# zumy_carrier_board.net
KiCad netlist of a schematic drawn in EAGLE
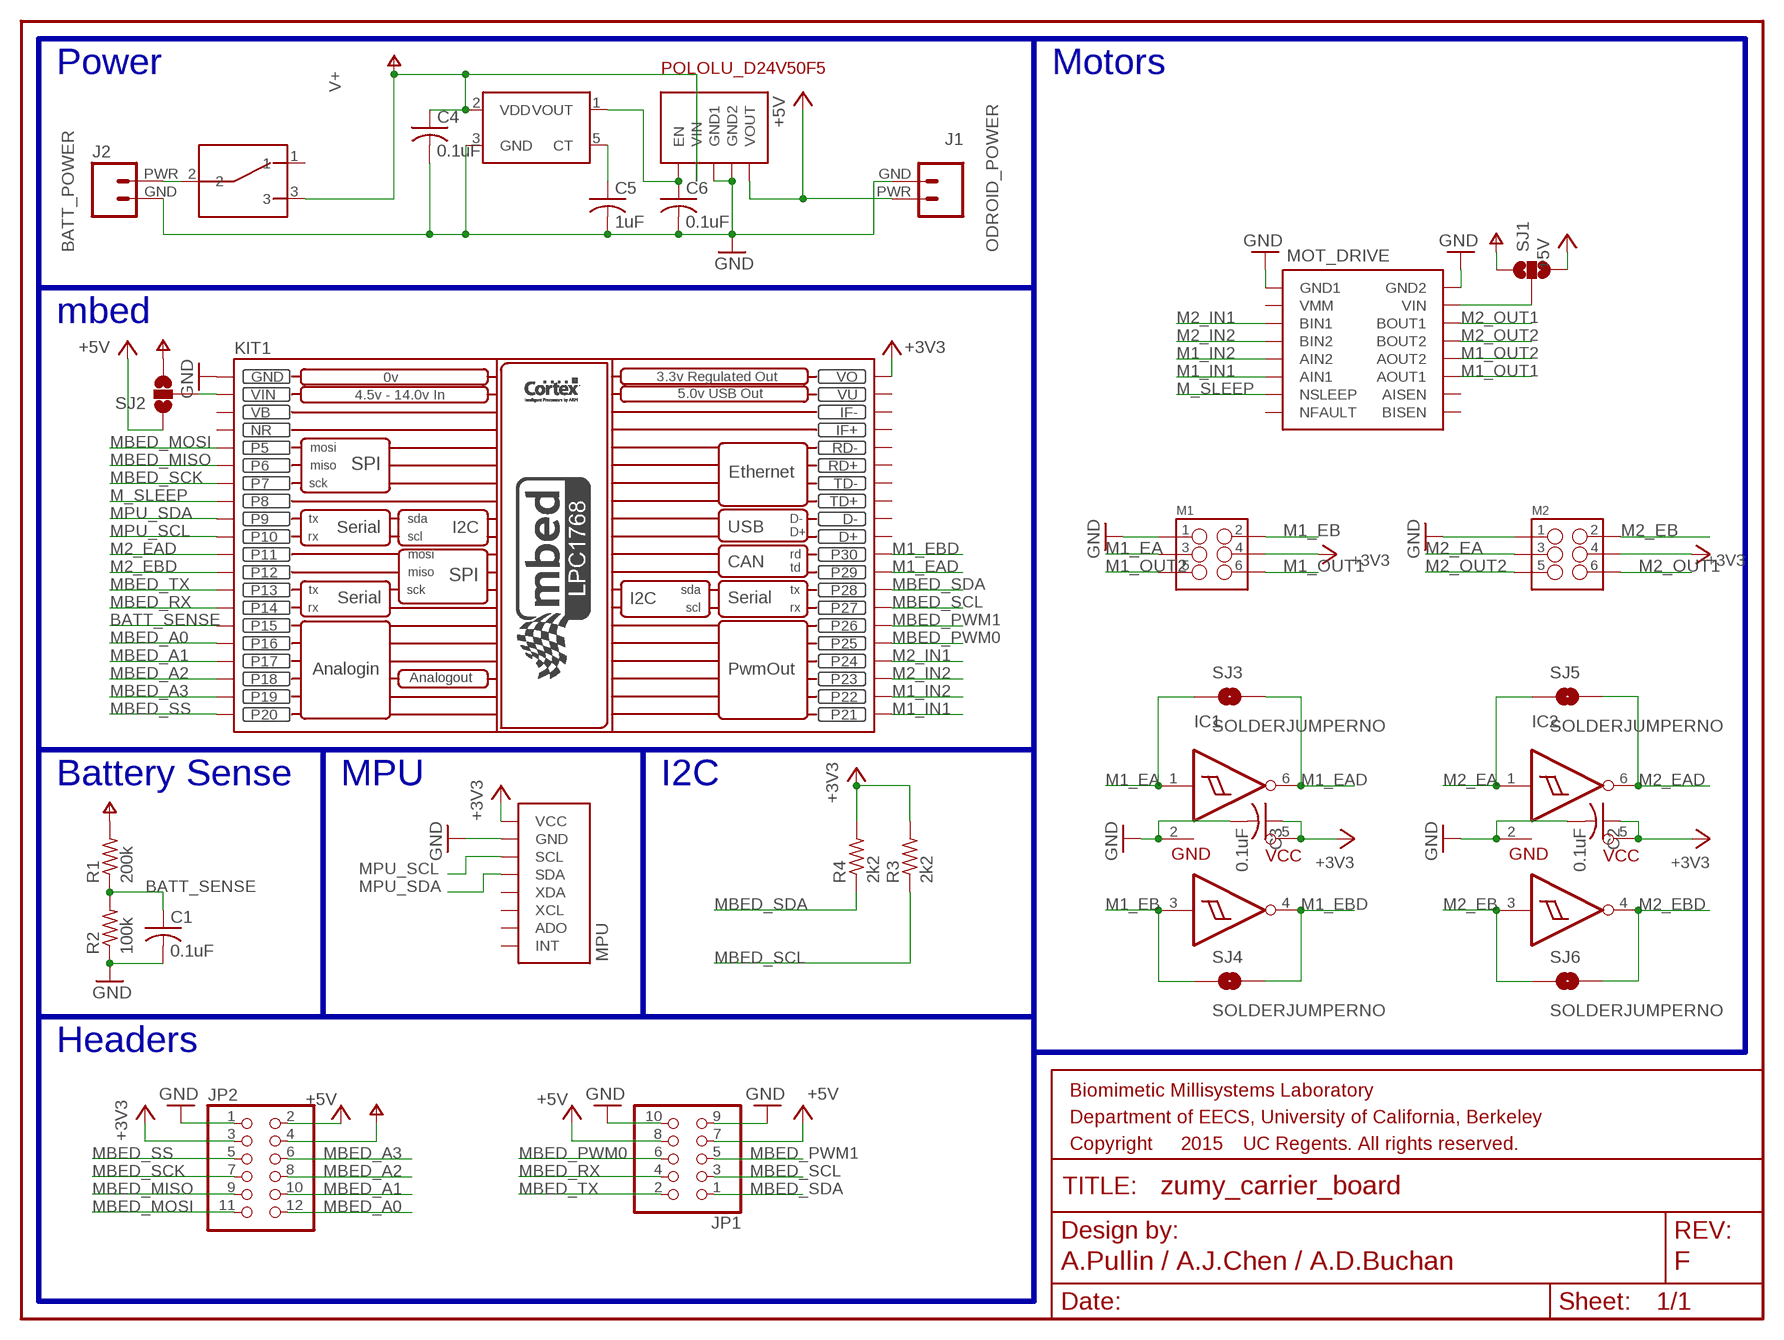
[diagram p0: schematic, sheet 1]

(export (version "E")
  (design (tool "Eeschema 10.0.6"))
  (components
    (comp (ref "C1")
      (value "0.1uF")
      (footprint "eagle-import:C1206")
      (libsource (lib "eagle-import") (part "C-USC1206"))
    )
    (comp (ref "C2")
      (value "0.1uF")
      (footprint "eagle-import:C1206")
      (libsource (lib "eagle-import") (part "C-USC1206"))
    )
    (comp (ref "C3")
      (value "0.1uF")
      (footprint "eagle-import:C1206")
      (libsource (lib "eagle-import") (part "C-USC1206"))
    )
    (comp (ref "C4")
      (value "0.1uF")
      (footprint "eagle-import:C1206")
      (libsource (lib "eagle-import") (part "C-USC1206"))
    )
    (comp (ref "C5")
      (value "1uF")
      (footprint "eagle-import:C1206")
      (libsource (lib "eagle-import") (part "C-USC1206"))
    )
    (comp (ref "C6")
      (value "0.1uF")
      (footprint "eagle-import:C1206")
      (libsource (lib "eagle-import") (part "C-USC1206"))
    )
    (comp (ref "IC1")
      (value "SN74AUP2G17")
      (footprint "eagle-import:SC-70-6")
      (libsource (lib "eagle-import") (part "SN74AUP2G17"))
    )
    (comp (ref "IC2")
      (value "SN74AUP2G17")
      (footprint "eagle-import:SC-70-6")
      (libsource (lib "eagle-import") (part "SN74AUP2G17"))
    )
    (comp (ref "J1")
      (value "ODROID_POWER")
      (footprint "eagle-import:ODOIRD_PWR")
      (libsource (lib "eagle-import") (part "ODROID_POWER"))
    )
    (comp (ref "J2")
      (value "BATT_POWER")
      (footprint "eagle-import:BATT_POWER")
      (libsource (lib "eagle-import") (part "BATT_POWER"))
    )
    (comp (ref "JP1")
      (value "PINHD-2X5")
      (footprint "eagle-import:2X05")
      (libsource (lib "eagle-import") (part "PINHD-2X5"))
    )
    (comp (ref "JP2")
      (value "PINHD-2X6")
      (footprint "eagle-import:2X06")
      (libsource (lib "eagle-import") (part "PINHD-2X6"))
    )
    (comp (ref "KIT1")
      (value "MBED_NXP_LPC1768")
      (footprint "eagle-import:MBED-KIT")
      (libsource (lib "eagle-import") (part "MBED_NXP_LPC1768"))
    )
    (comp (ref "M1")
      (value "M03X2SHROUD")
      (footprint "eagle-import:2X3-SHROUDED")
      (libsource (lib "eagle-import") (part "M03X2SHROUD"))
    )
    (comp (ref "M2")
      (value "M03X2SHROUD")
      (footprint "eagle-import:2X3-SHROUDED")
      (libsource (lib "eagle-import") (part "M03X2SHROUD"))
    )
    (comp (ref "MOT_DRIVE")
      (value "POLOLU_DRV8833_MODULE")
      (footprint "eagle-import:POLOLU_DRV8833_MODULE")
      (libsource (lib "eagle-import") (part "POLOLU_DRV8833_MODULE"))
    )
    (comp (ref "MPU")
      (value "ITG/MPU_MODULE")
      (footprint "eagle-import:ITG_MPU_MODULE")
      (libsource (lib "eagle-import") (part "ITG/MPU_MODULE"))
    )
    (comp (ref "R1")
      (value "200k")
      (footprint "eagle-import:R1206")
      (libsource (lib "eagle-import") (part "R-US_R1206"))
    )
    (comp (ref "R2")
      (value "100k")
      (footprint "eagle-import:R1206")
      (libsource (lib "eagle-import") (part "R-US_R1206"))
    )
    (comp (ref "R3")
      (value "2k2")
      (footprint "eagle-import:R1206")
      (libsource (lib "eagle-import") (part "R-US_R1206"))
    )
    (comp (ref "R4")
      (value "2k2")
      (footprint "eagle-import:R1206")
      (libsource (lib "eagle-import") (part "R-US_R1206"))
    )
    (comp (ref "SJ1")
      (value "SOLDERJUMPER_2WAYT")
      (footprint "eagle-import:SJ_2")
      (libsource (lib "eagle-import") (part "SOLDERJUMPER_2WAYT"))
    )
    (comp (ref "SJ2")
      (value "SOLDERJUMPER_2WAYT")
      (footprint "eagle-import:SJ_2")
      (libsource (lib "eagle-import") (part "SOLDERJUMPER_2WAYT"))
    )
    (comp (ref "SJ3")
      (value "SOLDERJUMPERNO")
      (footprint "eagle-import:SJ_2S-NO")
      (libsource (lib "eagle-import") (part "SOLDERJUMPERNO"))
    )
    (comp (ref "SJ4")
      (value "SOLDERJUMPERNO")
      (footprint "eagle-import:SJ_2S-NO")
      (libsource (lib "eagle-import") (part "SOLDERJUMPERNO"))
    )
    (comp (ref "SJ5")
      (value "SOLDERJUMPERNO")
      (footprint "eagle-import:SJ_2S-NO")
      (libsource (lib "eagle-import") (part "SOLDERJUMPERNO"))
    )
    (comp (ref "SJ6")
      (value "SOLDERJUMPERNO")
      (footprint "eagle-import:SJ_2S-NO")
      (libsource (lib "eagle-import") (part "SOLDERJUMPERNO"))
    )
    (comp (ref "SW1")
      (value "500SSP1S1M6QEA")
      (footprint "eagle-import:500SSP1S1M6QEA_SWITCH")
      (libsource (lib "eagle-import") (part "500SSP1S1M6QEA"))
    )
    (comp (ref "U$2")
      (value "BD5260G")
      (footprint "eagle-import:SOT23-5")
      (libsource (lib "eagle-import") (part "BD5260G"))
    )
    (comp (ref "U$5")
      (value "POLOLU_D24V50F5")
      (footprint "eagle-import:POLOLU_D24V50F5")
      (libsource (lib "eagle-import") (part "POLOLU_D24V50F5"))
    )
  )
  (nets
    (net (code "1") (name "+3V3") (class "Default")
      (node (ref "C2") (pin "1") (pinfunction "1_1") (pintype "passive"))
      (node (ref "C3") (pin "1") (pinfunction "1_1") (pintype "passive"))
      (node (ref "IC1") (pin "5") (pinfunction "VCC_5") (pintype "output"))
      (node (ref "IC2") (pin "5") (pinfunction "VCC_5") (pintype "output"))
      (node (ref "JP2") (pin "3") (pinfunction "3_3") (pintype "passive"))
      (node (ref "KIT1") (pin "VOUT") (pinfunction "VO_VOUT") (pintype "power_in"))
      (node (ref "M1") (pin "4") (pinfunction "4_4") (pintype "bidirectional"))
      (node (ref "M2") (pin "4") (pinfunction "4_4") (pintype "bidirectional"))
      (node (ref "MPU") (pin "VCC") (pinfunction "VCC_VCC") (pintype "bidirectional"))
      (node (ref "R3") (pin "2") (pinfunction "2_2") (pintype "passive"))
      (node (ref "R4") (pin "2") (pinfunction "2_2") (pintype "passive"))
    )
    (net (code "2") (name "+5V") (class "Default")
      (node (ref "J1") (pin "PWR") (pinfunction "PWR_PWR") (pintype "passive"))
      (node (ref "JP1") (pin "7") (pinfunction "7_7") (pintype "passive"))
      (node (ref "JP1") (pin "8") (pinfunction "8_8") (pintype "passive"))
      (node (ref "JP2") (pin "2") (pinfunction "2_2") (pintype "passive"))
      (node (ref "SJ1") (pin "3") (pinfunction "3_3") (pintype "passive"))
      (node (ref "SJ2") (pin "1") (pinfunction "1_1") (pintype "passive"))
      (node (ref "U$5") (pin "VOUT") (pinfunction "VOUT_VOUT") (pintype "bidirectional"))
    )
    (net (code "3") (name "/BATT_SENSE") (class "Default")
      (node (ref "C1") (pin "1") (pinfunction "1_1") (pintype "passive"))
      (node (ref "KIT1") (pin "P$15") (pinfunction "P15_P$15") (pintype "bidirectional"))
      (node (ref "R1") (pin "1") (pinfunction "1_1") (pintype "passive"))
      (node (ref "R2") (pin "2") (pinfunction "2_2") (pintype "passive"))
    )
    (net (code "4") (name "/M1_EA") (class "Default")
      (node (ref "IC1") (pin "1") (pinfunction "1A_1") (pintype "input"))
      (node (ref "M1") (pin "3") (pinfunction "3_3") (pintype "bidirectional"))
      (node (ref "SJ3") (pin "1") (pinfunction "1_1") (pintype "passive"))
    )
    (net (code "5") (name "/M1_EAD") (class "Default")
      (node (ref "IC1") (pin "6") (pinfunction "1Y_6") (pintype "output"))
      (node (ref "KIT1") (pin "P$29") (pinfunction "P29_P$29") (pintype "bidirectional"))
      (node (ref "SJ3") (pin "2") (pinfunction "2_2") (pintype "passive"))
    )
    (net (code "6") (name "/M1_EB") (class "Default")
      (node (ref "IC1") (pin "3") (pinfunction "2A_3") (pintype "input"))
      (node (ref "M1") (pin "2") (pinfunction "2_2") (pintype "bidirectional"))
      (node (ref "SJ4") (pin "1") (pinfunction "1_1") (pintype "passive"))
    )
    (net (code "7") (name "/M1_EBD") (class "Default")
      (node (ref "IC1") (pin "4") (pinfunction "2Y_4") (pintype "output"))
      (node (ref "KIT1") (pin "P$30") (pinfunction "P30_P$30") (pintype "bidirectional"))
      (node (ref "SJ4") (pin "2") (pinfunction "2_2") (pintype "passive"))
    )
    (net (code "8") (name "/M1_IN1") (class "Default")
      (node (ref "KIT1") (pin "P$21") (pinfunction "P21_P$21") (pintype "bidirectional"))
      (node (ref "MOT_DRIVE") (pin "AIN1") (pinfunction "AIN1_AIN1") (pintype "bidirectional"))
    )
    (net (code "9") (name "/M1_IN2") (class "Default")
      (node (ref "KIT1") (pin "P$22") (pinfunction "P22_P$22") (pintype "bidirectional"))
      (node (ref "MOT_DRIVE") (pin "AIN2") (pinfunction "AIN2_AIN2") (pintype "bidirectional"))
    )
    (net (code "10") (name "/M1_OUT1") (class "Default")
      (node (ref "M1") (pin "6") (pinfunction "6_6") (pintype "bidirectional"))
      (node (ref "MOT_DRIVE") (pin "AOUT1") (pinfunction "AOUT1_AOUT1") (pintype "bidirectional"))
    )
    (net (code "11") (name "/M1_OUT2") (class "Default")
      (node (ref "M1") (pin "5") (pinfunction "5_5") (pintype "bidirectional"))
      (node (ref "MOT_DRIVE") (pin "AOUT2") (pinfunction "AOUT2_AOUT2") (pintype "bidirectional"))
    )
    (net (code "12") (name "/M2_EA") (class "Default")
      (node (ref "IC2") (pin "1") (pinfunction "1A_1") (pintype "input"))
      (node (ref "M2") (pin "3") (pinfunction "3_3") (pintype "bidirectional"))
      (node (ref "SJ5") (pin "1") (pinfunction "1_1") (pintype "passive"))
    )
    (net (code "13") (name "/M2_EAD") (class "Default")
      (node (ref "IC2") (pin "6") (pinfunction "1Y_6") (pintype "output"))
      (node (ref "KIT1") (pin "P$11") (pinfunction "P11_P$11") (pintype "bidirectional"))
      (node (ref "SJ5") (pin "2") (pinfunction "2_2") (pintype "passive"))
    )
    (net (code "14") (name "/M2_EB") (class "Default")
      (node (ref "IC2") (pin "3") (pinfunction "2A_3") (pintype "input"))
      (node (ref "M2") (pin "2") (pinfunction "2_2") (pintype "bidirectional"))
      (node (ref "SJ6") (pin "1") (pinfunction "1_1") (pintype "passive"))
    )
    (net (code "15") (name "/M2_EBD") (class "Default")
      (node (ref "IC2") (pin "4") (pinfunction "2Y_4") (pintype "output"))
      (node (ref "KIT1") (pin "P$12") (pinfunction "P12_P$12") (pintype "bidirectional"))
      (node (ref "SJ6") (pin "2") (pinfunction "2_2") (pintype "passive"))
    )
    (net (code "16") (name "/M2_IN1") (class "Default")
      (node (ref "KIT1") (pin "P$24") (pinfunction "P24_P$24") (pintype "bidirectional"))
      (node (ref "MOT_DRIVE") (pin "BIN1") (pinfunction "BIN1_BIN1") (pintype "bidirectional"))
    )
    (net (code "17") (name "/M2_IN2") (class "Default")
      (node (ref "KIT1") (pin "P$23") (pinfunction "P23_P$23") (pintype "bidirectional"))
      (node (ref "MOT_DRIVE") (pin "BIN2") (pinfunction "BIN2_BIN2") (pintype "bidirectional"))
    )
    (net (code "18") (name "/M2_OUT1") (class "Default")
      (node (ref "M2") (pin "6") (pinfunction "6_6") (pintype "bidirectional"))
      (node (ref "MOT_DRIVE") (pin "BOUT1") (pinfunction "BOUT1_BOUT1") (pintype "bidirectional"))
    )
    (net (code "19") (name "/M2_OUT2") (class "Default")
      (node (ref "M2") (pin "5") (pinfunction "5_5") (pintype "bidirectional"))
      (node (ref "MOT_DRIVE") (pin "BOUT2") (pinfunction "BOUT2_BOUT2") (pintype "bidirectional"))
    )
    (net (code "20") (name "/MBED_A0") (class "Default")
      (node (ref "JP2") (pin "12") (pinfunction "12_12") (pintype "passive"))
      (node (ref "KIT1") (pin "P$16") (pinfunction "P16_P$16") (pintype "bidirectional"))
    )
    (net (code "21") (name "/MBED_A1") (class "Default")
      (node (ref "JP2") (pin "10") (pinfunction "10_10") (pintype "passive"))
      (node (ref "KIT1") (pin "P$17") (pinfunction "P17_P$17") (pintype "bidirectional"))
    )
    (net (code "22") (name "/MBED_A2") (class "Default")
      (node (ref "JP2") (pin "8") (pinfunction "8_8") (pintype "passive"))
      (node (ref "KIT1") (pin "P$18") (pinfunction "P18_P$18") (pintype "bidirectional"))
    )
    (net (code "23") (name "/MBED_A3") (class "Default")
      (node (ref "JP2") (pin "6") (pinfunction "6_6") (pintype "passive"))
      (node (ref "KIT1") (pin "P$19") (pinfunction "P19_P$19") (pintype "bidirectional"))
    )
    (net (code "24") (name "/MBED_MISO") (class "Default")
      (node (ref "JP2") (pin "9") (pinfunction "9_9") (pintype "passive"))
      (node (ref "KIT1") (pin "P$6") (pinfunction "P6_P$6") (pintype "bidirectional"))
    )
    (net (code "25") (name "/MBED_MOSI") (class "Default")
      (node (ref "JP2") (pin "11") (pinfunction "11_11") (pintype "passive"))
      (node (ref "KIT1") (pin "P$5") (pinfunction "P5_P$5") (pintype "bidirectional"))
    )
    (net (code "26") (name "/MBED_PWM0") (class "Default")
      (node (ref "JP1") (pin "6") (pinfunction "6_6") (pintype "passive"))
      (node (ref "KIT1") (pin "P$25") (pinfunction "P25_P$25") (pintype "bidirectional"))
    )
    (net (code "27") (name "/MBED_PWM1") (class "Default")
      (node (ref "JP1") (pin "5") (pinfunction "5_5") (pintype "passive"))
      (node (ref "KIT1") (pin "P$26") (pinfunction "P26_P$26") (pintype "bidirectional"))
    )
    (net (code "28") (name "/MBED_RX") (class "Default")
      (node (ref "JP1") (pin "4") (pinfunction "4_4") (pintype "passive"))
      (node (ref "KIT1") (pin "P$14") (pinfunction "P14_P$14") (pintype "bidirectional"))
    )
    (net (code "29") (name "/MBED_SCK") (class "Default")
      (node (ref "JP2") (pin "7") (pinfunction "7_7") (pintype "passive"))
      (node (ref "KIT1") (pin "P$7") (pinfunction "P7_P$7") (pintype "bidirectional"))
    )
    (net (code "30") (name "/MBED_SCL") (class "Default")
      (node (ref "JP1") (pin "3") (pinfunction "3_3") (pintype "passive"))
      (node (ref "KIT1") (pin "P$27") (pinfunction "P27_P$27") (pintype "bidirectional"))
      (node (ref "R3") (pin "1") (pinfunction "1_1") (pintype "passive"))
    )
    (net (code "31") (name "/MBED_SDA") (class "Default")
      (node (ref "JP1") (pin "1") (pinfunction "1_1") (pintype "passive"))
      (node (ref "KIT1") (pin "P$28") (pinfunction "P28_P$28") (pintype "bidirectional"))
      (node (ref "R4") (pin "1") (pinfunction "1_1") (pintype "passive"))
    )
    (net (code "32") (name "/MBED_SS") (class "Default")
      (node (ref "JP2") (pin "5") (pinfunction "5_5") (pintype "passive"))
      (node (ref "KIT1") (pin "P$20") (pinfunction "P20_P$20") (pintype "bidirectional"))
    )
    (net (code "33") (name "/MBED_TX") (class "Default")
      (node (ref "JP1") (pin "2") (pinfunction "2_2") (pintype "passive"))
      (node (ref "KIT1") (pin "P$13") (pinfunction "P13_P$13") (pintype "bidirectional"))
    )
    (net (code "34") (name "/MPU_SCL") (class "Default")
      (node (ref "KIT1") (pin "P$10") (pinfunction "P10_P$10") (pintype "bidirectional"))
      (node (ref "MPU") (pin "SCL") (pinfunction "SCL_SCL") (pintype "bidirectional"))
    )
    (net (code "35") (name "/MPU_SDA") (class "Default")
      (node (ref "KIT1") (pin "P$9") (pinfunction "P9_P$9") (pintype "bidirectional"))
      (node (ref "MPU") (pin "SDA") (pinfunction "SDA_SDA") (pintype "bidirectional"))
    )
    (net (code "36") (name "/M_SLEEP") (class "Default")
      (node (ref "KIT1") (pin "P$8") (pinfunction "P8_P$8") (pintype "bidirectional"))
      (node (ref "MOT_DRIVE") (pin "NSLEEP") (pinfunction "NSLEEP_NSLEEP") (pintype "bidirectional"))
    )
    (net (code "37") (name "/NR") (class "Default")
      (node (ref "KIT1") (pin "NR") (pinfunction "NR_NR") (pintype "power_in"))
    )
    (net (code "38") (name "/VB") (class "Default")
      (node (ref "KIT1") (pin "VB") (pinfunction "VB_VB") (pintype "power_in"))
    )
    (net (code "39") (name "/VU") (class "Default")
      (node (ref "KIT1") (pin "VU") (pinfunction "VU_VU") (pintype "power_in"))
    )
    (net (code "40") (name "GND") (class "Default")
      (node (ref "C1") (pin "2") (pinfunction "2_2") (pintype "passive"))
      (node (ref "C2") (pin "2") (pinfunction "2_2") (pintype "passive"))
      (node (ref "C3") (pin "2") (pinfunction "2_2") (pintype "passive"))
      (node (ref "C4") (pin "2") (pinfunction "2_2") (pintype "passive"))
      (node (ref "C5") (pin "2") (pinfunction "2_2") (pintype "passive"))
      (node (ref "C6") (pin "2") (pinfunction "2_2") (pintype "passive"))
      (node (ref "IC1") (pin "2") (pinfunction "GND_2") (pintype "input"))
      (node (ref "IC2") (pin "2") (pinfunction "GND_2") (pintype "input"))
      (node (ref "J1") (pin "GND") (pinfunction "GND_GND") (pintype "passive"))
      (node (ref "J2") (pin "GND") (pinfunction "GND_GND") (pintype "passive"))
      (node (ref "JP1") (pin "10") (pinfunction "10_10") (pintype "passive"))
      (node (ref "JP1") (pin "9") (pinfunction "9_9") (pintype "passive"))
      (node (ref "JP2") (pin "1") (pinfunction "1_1") (pintype "passive"))
      (node (ref "KIT1") (pin "GND") (pinfunction "GND_GND") (pintype "power_in"))
      (node (ref "M1") (pin "1") (pinfunction "1_1") (pintype "bidirectional"))
      (node (ref "M2") (pin "1") (pinfunction "1_1") (pintype "bidirectional"))
      (node (ref "MOT_DRIVE") (pin "GND1") (pinfunction "GND1_GND1") (pintype "bidirectional"))
      (node (ref "MOT_DRIVE") (pin "GND2") (pinfunction "GND2_GND2") (pintype "bidirectional"))
      (node (ref "MPU") (pin "GND") (pinfunction "GND_GND") (pintype "bidirectional"))
      (node (ref "R2") (pin "1") (pinfunction "1_1") (pintype "passive"))
      (node (ref "U$2") (pin "3") (pinfunction "GND_3") (pintype "bidirectional"))
      (node (ref "U$5") (pin "GND1") (pinfunction "GND1_GND1") (pintype "bidirectional"))
      (node (ref "U$5") (pin "GND2") (pinfunction "GND2_GND2") (pintype "bidirectional"))
    )
    (net (code "41") (name "Net-(J2-PadPWR)") (class "Default")
      (node (ref "J2") (pin "PWR") (pinfunction "PWR_PWR") (pintype "passive"))
      (node (ref "SW1") (pin "2") (pinfunction "2_2") (pintype "bidirectional"))
    )
    (net (code "42") (name "Net-(KIT1-PadVIN)") (class "Default")
      (node (ref "KIT1") (pin "VIN") (pinfunction "VIN_VIN") (pintype "power_in"))
      (node (ref "SJ2") (pin "2") (pinfunction "2_2") (pintype "passive"))
    )
    (net (code "43") (name "Net-(MOT_DRIVE-PadVIN)") (class "Default")
      (node (ref "MOT_DRIVE") (pin "VIN") (pinfunction "VIN_VIN") (pintype "bidirectional"))
      (node (ref "SJ1") (pin "2") (pinfunction "2_2") (pintype "passive"))
    )
    (net (code "44") (name "Net-(U$2-CT)") (class "Default")
      (node (ref "C5") (pin "1") (pinfunction "1_1") (pintype "passive"))
      (node (ref "U$2") (pin "5") (pinfunction "CT_5") (pintype "bidirectional"))
    )
    (net (code "45") (name "Net-(U$2-VOUT)") (class "Default")
      (node (ref "C6") (pin "1") (pinfunction "1_1") (pintype "passive"))
      (node (ref "U$2") (pin "1") (pinfunction "VOUT_1") (pintype "bidirectional"))
      (node (ref "U$5") (pin "EN") (pinfunction "EN_EN") (pintype "bidirectional"))
    )
    (net (code "46") (name "V+") (class "Default")
      (node (ref "C4") (pin "1") (pinfunction "1_1") (pintype "passive"))
      (node (ref "JP2") (pin "4") (pinfunction "4_4") (pintype "passive"))
      (node (ref "R1") (pin "2") (pinfunction "2_2") (pintype "passive"))
      (node (ref "SJ1") (pin "1") (pinfunction "1_1") (pintype "passive"))
      (node (ref "SJ2") (pin "3") (pinfunction "3_3") (pintype "passive"))
      (node (ref "SW1") (pin "3") (pinfunction "3_3") (pintype "bidirectional"))
      (node (ref "U$2") (pin "2") (pinfunction "VDD_2") (pintype "bidirectional"))
      (node (ref "U$5") (pin "VIN") (pinfunction "VIN_VIN") (pintype "bidirectional"))
    )
    (net (code "47") (name "unconnected-(KIT1-PadD+)") (class "Default")
      (node (ref "KIT1") (pin "D+") (pinfunction "D+_D+") (pintype "bidirectional"))
    )
    (net (code "48") (name "unconnected-(KIT1-PadD-)") (class "Default")
      (node (ref "KIT1") (pin "D-") (pinfunction "D-_D-") (pintype "bidirectional"))
    )
    (net (code "49") (name "unconnected-(KIT1-PadIF+)") (class "Default")
      (node (ref "KIT1") (pin "IF+") (pinfunction "IF+_IF+") (pintype "bidirectional"))
    )
    (net (code "50") (name "unconnected-(KIT1-PadIF-)") (class "Default")
      (node (ref "KIT1") (pin "IF-") (pinfunction "IF-_IF-") (pintype "bidirectional"))
    )
    (net (code "51") (name "unconnected-(KIT1-PadRD+)") (class "Default")
      (node (ref "KIT1") (pin "RD+") (pinfunction "RD+_RD+") (pintype "bidirectional"))
    )
    (net (code "52") (name "unconnected-(KIT1-PadRD-)") (class "Default")
      (node (ref "KIT1") (pin "RD-") (pinfunction "RD-_RD-") (pintype "bidirectional"))
    )
    (net (code "53") (name "unconnected-(KIT1-PadTD+)") (class "Default")
      (node (ref "KIT1") (pin "TD+") (pinfunction "TD+_TD+") (pintype "bidirectional"))
    )
    (net (code "54") (name "unconnected-(KIT1-PadTD-)") (class "Default")
      (node (ref "KIT1") (pin "TD-") (pinfunction "TD-_TD-") (pintype "bidirectional"))
    )
    (net (code "55") (name "unconnected-(MOT_DRIVE-PadAISEN)") (class "Default")
      (node (ref "MOT_DRIVE") (pin "AISEN") (pinfunction "AISEN_AISEN") (pintype "bidirectional"))
    )
    (net (code "56") (name "unconnected-(MOT_DRIVE-PadBISEN)") (class "Default")
      (node (ref "MOT_DRIVE") (pin "BISEN") (pinfunction "BISEN_BISEN") (pintype "bidirectional"))
    )
    (net (code "57") (name "unconnected-(MOT_DRIVE-PadNFAULT)") (class "Default")
      (node (ref "MOT_DRIVE") (pin "NFAULT") (pinfunction "NFAULT_NFAULT") (pintype "bidirectional"))
    )
    (net (code "58") (name "unconnected-(MOT_DRIVE-PadVMM)") (class "Default")
      (node (ref "MOT_DRIVE") (pin "VMM") (pinfunction "VMM_VMM") (pintype "bidirectional"))
    )
    (net (code "59") (name "unconnected-(MPU-PadADO)") (class "Default")
      (node (ref "MPU") (pin "ADO") (pinfunction "ADO_ADO") (pintype "bidirectional"))
    )
    (net (code "60") (name "unconnected-(MPU-PadINT)") (class "Default")
      (node (ref "MPU") (pin "INT") (pinfunction "INT_INT") (pintype "bidirectional"))
    )
    (net (code "61") (name "unconnected-(MPU-PadXCL)") (class "Default")
      (node (ref "MPU") (pin "XCL") (pinfunction "XCL_XCL") (pintype "bidirectional"))
    )
    (net (code "62") (name "unconnected-(MPU-PadXDA)") (class "Default")
      (node (ref "MPU") (pin "XDA") (pinfunction "XDA_XDA") (pintype "bidirectional"))
    )
    (net (code "63") (name "unconnected-(SW1-Pad1)") (class "Default")
      (node (ref "SW1") (pin "1") (pinfunction "1_1") (pintype "bidirectional"))
    )
  )
)
